# Sheet4.net
KiCad netlist of a schematic drawn in Altium Designer
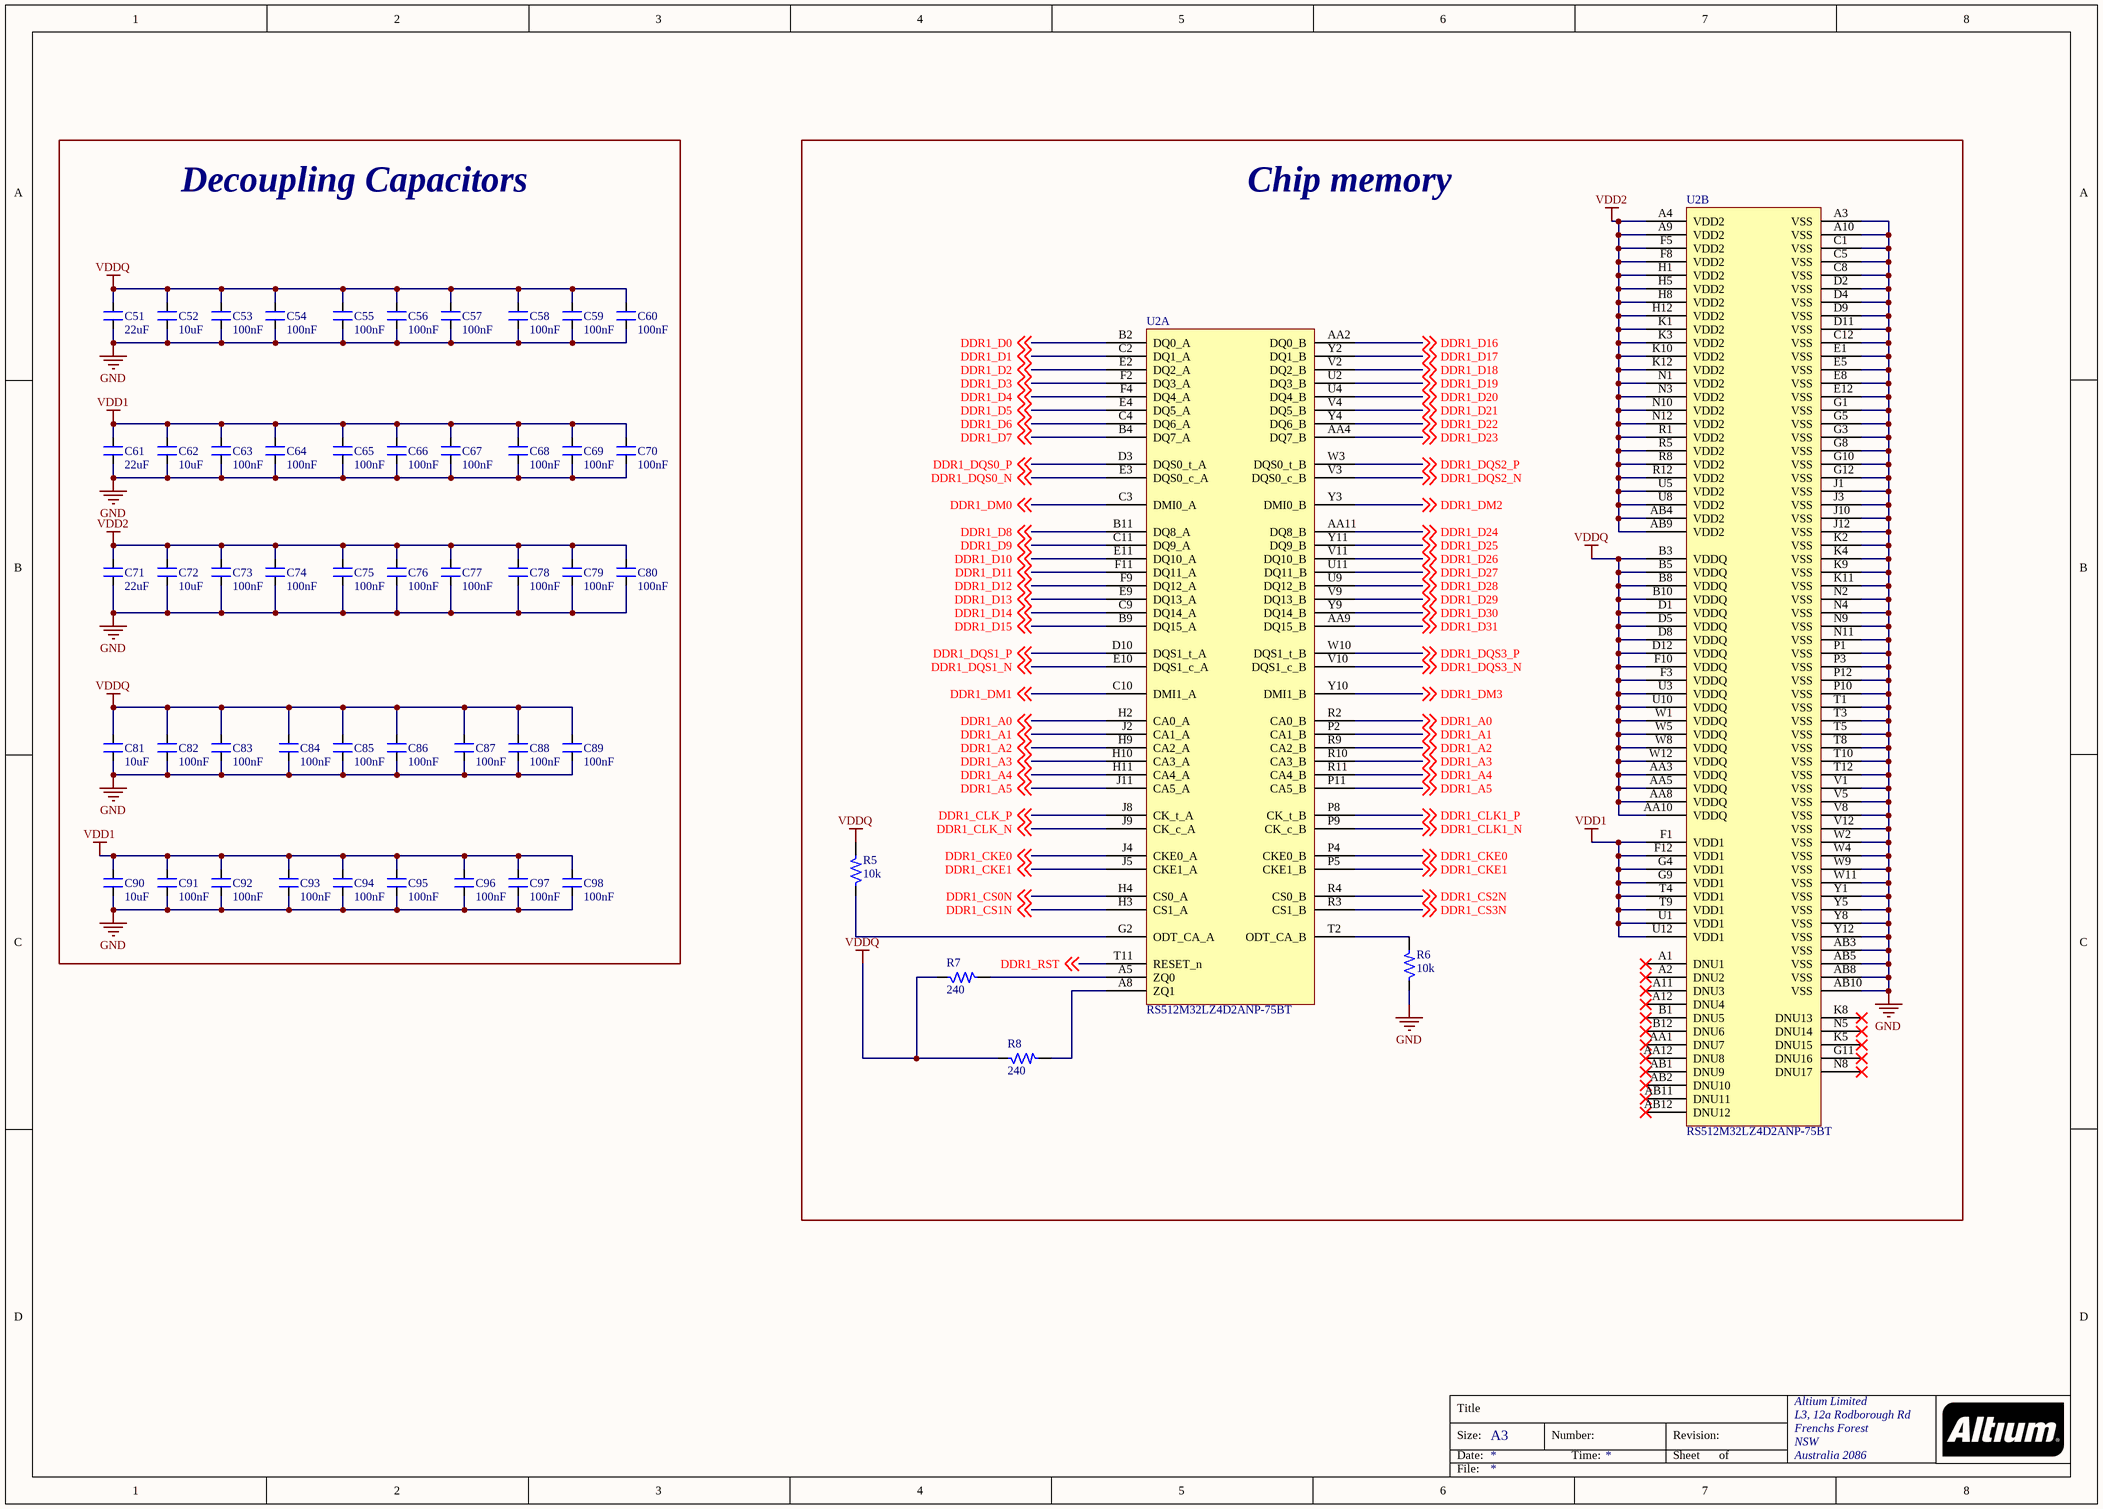
[diagram p0: Sheet4.SchDoc]

(export (version "E")
  (design (tool "Eeschema 10.0.6"))
  (components
    (comp (ref "C51")
      (value "22uF")
      (footprint "CAP_0603")
      (description "22µF ±20% 10V Ceramic Capacitor X5R 0603 (1608 Metric)")
      (fields
        (field (name "MANUFACTURER") "Murata Electronics")
        (field (name "MANUFACTURER PART NUMBER") "GRM188R61A226ME15D")
      )
      (libsource (lib "EsteemPCB_SOM_Course_intlib") (part "CAP_22uF-10V-20%-0603"))
    )
    (comp (ref "C52")
      (value "10uF")
      (footprint "CAP_0603")
      (description "10µF ±10% 10V Ceramic Capacitor X5R 0603 (1608 Metric)")
      (fields
        (field (name "MANUFACTURER PART NUMBER") "GRM188R61A106KE69J")
        (field (name "MANUFACTURER") "Murata Electronics")
      )
      (libsource (lib "EsteemPCB_SOM_Course_intlib") (part "CAP_10uF-10V-10%-0603"))
    )
    (comp (ref "C53")
      (value "100nF")
      (footprint "CAP_0201")
      (description "0.1µF ±10% 25V Ceramic Capacitor X5R 0201 (0603 Metric)")
      (fields
        (field (name "MANUFACTURER") "TDK Corporation")
        (field (name "MANUFACTURER PART NUMBER") "C0603X5R1E104K030BB")
      )
      (libsource (lib "EsteemPCB_SOM_Course_intlib") (part "CAP_100nF-25V-10%-0201"))
    )
    (comp (ref "C54")
      (value "100nF")
      (footprint "CAP_0201")
      (description "0.1µF ±10% 25V Ceramic Capacitor X5R 0201 (0603 Metric)")
      (fields
        (field (name "MANUFACTURER") "TDK Corporation")
        (field (name "MANUFACTURER PART NUMBER") "C0603X5R1E104K030BB")
      )
      (libsource (lib "EsteemPCB_SOM_Course_intlib") (part "CAP_100nF-25V-10%-0201"))
    )
    (comp (ref "C55")
      (value "100nF")
      (footprint "CAP_0201")
      (description "0.1µF ±10% 25V Ceramic Capacitor X5R 0201 (0603 Metric)")
      (fields
        (field (name "MANUFACTURER") "TDK Corporation")
        (field (name "MANUFACTURER PART NUMBER") "C0603X5R1E104K030BB")
      )
      (libsource (lib "EsteemPCB_SOM_Course_intlib") (part "CAP_100nF-25V-10%-0201"))
    )
    (comp (ref "C56")
      (value "100nF")
      (footprint "CAP_0201")
      (description "0.1µF ±10% 25V Ceramic Capacitor X5R 0201 (0603 Metric)")
      (fields
        (field (name "MANUFACTURER") "TDK Corporation")
        (field (name "MANUFACTURER PART NUMBER") "C0603X5R1E104K030BB")
      )
      (libsource (lib "EsteemPCB_SOM_Course_intlib") (part "CAP_100nF-25V-10%-0201"))
    )
    (comp (ref "C57")
      (value "100nF")
      (footprint "CAP_0201")
      (description "0.1µF ±10% 25V Ceramic Capacitor X5R 0201 (0603 Metric)")
      (fields
        (field (name "MANUFACTURER") "TDK Corporation")
        (field (name "MANUFACTURER PART NUMBER") "C0603X5R1E104K030BB")
      )
      (libsource (lib "EsteemPCB_SOM_Course_intlib") (part "CAP_100nF-25V-10%-0201"))
    )
    (comp (ref "C58")
      (value "100nF")
      (footprint "CAP_0201")
      (description "0.1µF ±10% 25V Ceramic Capacitor X5R 0201 (0603 Metric)")
      (fields
        (field (name "MANUFACTURER") "TDK Corporation")
        (field (name "MANUFACTURER PART NUMBER") "C0603X5R1E104K030BB")
      )
      (libsource (lib "EsteemPCB_SOM_Course_intlib") (part "CAP_100nF-25V-10%-0201"))
    )
    (comp (ref "C59")
      (value "100nF")
      (footprint "CAP_0201")
      (description "0.1µF ±10% 25V Ceramic Capacitor X5R 0201 (0603 Metric)")
      (fields
        (field (name "MANUFACTURER") "TDK Corporation")
        (field (name "MANUFACTURER PART NUMBER") "C0603X5R1E104K030BB")
      )
      (libsource (lib "EsteemPCB_SOM_Course_intlib") (part "CAP_100nF-25V-10%-0201"))
    )
    (comp (ref "C60")
      (value "100nF")
      (footprint "CAP_0201")
      (description "0.1µF ±10% 25V Ceramic Capacitor X5R 0201 (0603 Metric)")
      (fields
        (field (name "MANUFACTURER") "TDK Corporation")
        (field (name "MANUFACTURER PART NUMBER") "C0603X5R1E104K030BB")
      )
      (libsource (lib "EsteemPCB_SOM_Course_intlib") (part "CAP_100nF-25V-10%-0201"))
    )
    (comp (ref "C61")
      (value "22uF")
      (footprint "CAP_0603")
      (description "22µF ±20% 10V Ceramic Capacitor X5R 0603 (1608 Metric)")
      (fields
        (field (name "MANUFACTURER") "Murata Electronics")
        (field (name "MANUFACTURER PART NUMBER") "GRM188R61A226ME15D")
      )
      (libsource (lib "EsteemPCB_SOM_Course_intlib") (part "CAP_22uF-10V-20%-0603"))
    )
    (comp (ref "C62")
      (value "10uF")
      (footprint "CAP_0603")
      (description "10µF ±10% 10V Ceramic Capacitor X5R 0603 (1608 Metric)")
      (fields
        (field (name "MANUFACTURER PART NUMBER") "GRM188R61A106KE69J")
        (field (name "MANUFACTURER") "Murata Electronics")
      )
      (libsource (lib "EsteemPCB_SOM_Course_intlib") (part "CAP_10uF-10V-10%-0603"))
    )
    (comp (ref "C63")
      (value "100nF")
      (footprint "CAP_0201")
      (description "0.1µF ±10% 25V Ceramic Capacitor X5R 0201 (0603 Metric)")
      (fields
        (field (name "MANUFACTURER") "TDK Corporation")
        (field (name "MANUFACTURER PART NUMBER") "C0603X5R1E104K030BB")
      )
      (libsource (lib "EsteemPCB_SOM_Course_intlib") (part "CAP_100nF-25V-10%-0201"))
    )
    (comp (ref "C64")
      (value "100nF")
      (footprint "CAP_0201")
      (description "0.1µF ±10% 25V Ceramic Capacitor X5R 0201 (0603 Metric)")
      (fields
        (field (name "MANUFACTURER") "TDK Corporation")
        (field (name "MANUFACTURER PART NUMBER") "C0603X5R1E104K030BB")
      )
      (libsource (lib "EsteemPCB_SOM_Course_intlib") (part "CAP_100nF-25V-10%-0201"))
    )
    (comp (ref "C65")
      (value "100nF")
      (footprint "CAP_0201")
      (description "0.1µF ±10% 25V Ceramic Capacitor X5R 0201 (0603 Metric)")
      (fields
        (field (name "MANUFACTURER") "TDK Corporation")
        (field (name "MANUFACTURER PART NUMBER") "C0603X5R1E104K030BB")
      )
      (libsource (lib "EsteemPCB_SOM_Course_intlib") (part "CAP_100nF-25V-10%-0201"))
    )
    (comp (ref "C66")
      (value "100nF")
      (footprint "CAP_0201")
      (description "0.1µF ±10% 25V Ceramic Capacitor X5R 0201 (0603 Metric)")
      (fields
        (field (name "MANUFACTURER") "TDK Corporation")
        (field (name "MANUFACTURER PART NUMBER") "C0603X5R1E104K030BB")
      )
      (libsource (lib "EsteemPCB_SOM_Course_intlib") (part "CAP_100nF-25V-10%-0201"))
    )
    (comp (ref "C67")
      (value "100nF")
      (footprint "CAP_0201")
      (description "0.1µF ±10% 25V Ceramic Capacitor X5R 0201 (0603 Metric)")
      (fields
        (field (name "MANUFACTURER") "TDK Corporation")
        (field (name "MANUFACTURER PART NUMBER") "C0603X5R1E104K030BB")
      )
      (libsource (lib "EsteemPCB_SOM_Course_intlib") (part "CAP_100nF-25V-10%-0201"))
    )
    (comp (ref "C68")
      (value "100nF")
      (footprint "CAP_0201")
      (description "0.1µF ±10% 25V Ceramic Capacitor X5R 0201 (0603 Metric)")
      (fields
        (field (name "MANUFACTURER") "TDK Corporation")
        (field (name "MANUFACTURER PART NUMBER") "C0603X5R1E104K030BB")
      )
      (libsource (lib "EsteemPCB_SOM_Course_intlib") (part "CAP_100nF-25V-10%-0201"))
    )
    (comp (ref "C69")
      (value "100nF")
      (footprint "CAP_0201")
      (description "0.1µF ±10% 25V Ceramic Capacitor X5R 0201 (0603 Metric)")
      (fields
        (field (name "MANUFACTURER") "TDK Corporation")
        (field (name "MANUFACTURER PART NUMBER") "C0603X5R1E104K030BB")
      )
      (libsource (lib "EsteemPCB_SOM_Course_intlib") (part "CAP_100nF-25V-10%-0201"))
    )
    (comp (ref "C70")
      (value "100nF")
      (footprint "CAP_0201")
      (description "0.1µF ±10% 25V Ceramic Capacitor X5R 0201 (0603 Metric)")
      (fields
        (field (name "MANUFACTURER") "TDK Corporation")
        (field (name "MANUFACTURER PART NUMBER") "C0603X5R1E104K030BB")
      )
      (libsource (lib "EsteemPCB_SOM_Course_intlib") (part "CAP_100nF-25V-10%-0201"))
    )
    (comp (ref "C71")
      (value "22uF")
      (footprint "CAP_0603")
      (description "22µF ±20% 10V Ceramic Capacitor X5R 0603 (1608 Metric)")
      (fields
        (field (name "MANUFACTURER") "Murata Electronics")
        (field (name "MANUFACTURER PART NUMBER") "GRM188R61A226ME15D")
      )
      (libsource (lib "EsteemPCB_SOM_Course_intlib") (part "CAP_22uF-10V-20%-0603"))
    )
    (comp (ref "C72")
      (value "10uF")
      (footprint "CAP_0603")
      (description "10µF ±10% 10V Ceramic Capacitor X5R 0603 (1608 Metric)")
      (fields
        (field (name "MANUFACTURER PART NUMBER") "GRM188R61A106KE69J")
        (field (name "MANUFACTURER") "Murata Electronics")
      )
      (libsource (lib "EsteemPCB_SOM_Course_intlib") (part "CAP_10uF-10V-10%-0603"))
    )
    (comp (ref "C73")
      (value "100nF")
      (footprint "CAP_0201")
      (description "0.1µF ±10% 25V Ceramic Capacitor X5R 0201 (0603 Metric)")
      (fields
        (field (name "MANUFACTURER") "TDK Corporation")
        (field (name "MANUFACTURER PART NUMBER") "C0603X5R1E104K030BB")
      )
      (libsource (lib "EsteemPCB_SOM_Course_intlib") (part "CAP_100nF-25V-10%-0201"))
    )
    (comp (ref "C74")
      (value "100nF")
      (footprint "CAP_0201")
      (description "0.1µF ±10% 25V Ceramic Capacitor X5R 0201 (0603 Metric)")
      (fields
        (field (name "MANUFACTURER") "TDK Corporation")
        (field (name "MANUFACTURER PART NUMBER") "C0603X5R1E104K030BB")
      )
      (libsource (lib "EsteemPCB_SOM_Course_intlib") (part "CAP_100nF-25V-10%-0201"))
    )
    (comp (ref "C75")
      (value "100nF")
      (footprint "CAP_0201")
      (description "0.1µF ±10% 25V Ceramic Capacitor X5R 0201 (0603 Metric)")
      (fields
        (field (name "MANUFACTURER") "TDK Corporation")
        (field (name "MANUFACTURER PART NUMBER") "C0603X5R1E104K030BB")
      )
      (libsource (lib "EsteemPCB_SOM_Course_intlib") (part "CAP_100nF-25V-10%-0201"))
    )
    (comp (ref "C76")
      (value "100nF")
      (footprint "CAP_0201")
      (description "0.1µF ±10% 25V Ceramic Capacitor X5R 0201 (0603 Metric)")
      (fields
        (field (name "MANUFACTURER") "TDK Corporation")
        (field (name "MANUFACTURER PART NUMBER") "C0603X5R1E104K030BB")
      )
      (libsource (lib "EsteemPCB_SOM_Course_intlib") (part "CAP_100nF-25V-10%-0201"))
    )
    (comp (ref "C77")
      (value "100nF")
      (footprint "CAP_0201")
      (description "0.1µF ±10% 25V Ceramic Capacitor X5R 0201 (0603 Metric)")
      (fields
        (field (name "MANUFACTURER") "TDK Corporation")
        (field (name "MANUFACTURER PART NUMBER") "C0603X5R1E104K030BB")
      )
      (libsource (lib "EsteemPCB_SOM_Course_intlib") (part "CAP_100nF-25V-10%-0201"))
    )
    (comp (ref "C78")
      (value "100nF")
      (footprint "CAP_0201")
      (description "0.1µF ±10% 25V Ceramic Capacitor X5R 0201 (0603 Metric)")
      (fields
        (field (name "MANUFACTURER") "TDK Corporation")
        (field (name "MANUFACTURER PART NUMBER") "C0603X5R1E104K030BB")
      )
      (libsource (lib "EsteemPCB_SOM_Course_intlib") (part "CAP_100nF-25V-10%-0201"))
    )
    (comp (ref "C79")
      (value "100nF")
      (footprint "CAP_0201")
      (description "0.1µF ±10% 25V Ceramic Capacitor X5R 0201 (0603 Metric)")
      (fields
        (field (name "MANUFACTURER") "TDK Corporation")
        (field (name "MANUFACTURER PART NUMBER") "C0603X5R1E104K030BB")
      )
      (libsource (lib "EsteemPCB_SOM_Course_intlib") (part "CAP_100nF-25V-10%-0201"))
    )
    (comp (ref "C80")
      (value "100nF")
      (footprint "CAP_0201")
      (description "0.1µF ±10% 25V Ceramic Capacitor X5R 0201 (0603 Metric)")
      (fields
        (field (name "MANUFACTURER") "TDK Corporation")
        (field (name "MANUFACTURER PART NUMBER") "C0603X5R1E104K030BB")
      )
      (libsource (lib "EsteemPCB_SOM_Course_intlib") (part "CAP_100nF-25V-10%-0201"))
    )
    (comp (ref "C81")
      (value "10uF")
      (footprint "CAP_0603")
      (description "10µF ±10% 10V Ceramic Capacitor X5R 0603 (1608 Metric)")
      (fields
        (field (name "MANUFACTURER PART NUMBER") "GRM188R61A106KE69J")
        (field (name "MANUFACTURER") "Murata Electronics")
      )
      (libsource (lib "EsteemPCB_SOM_Course_intlib") (part "CAP_10uF-10V-10%-0603"))
    )
    (comp (ref "C82")
      (value "100nF")
      (footprint "CAP_0201")
      (description "0.1µF ±10% 25V Ceramic Capacitor X5R 0201 (0603 Metric)")
      (fields
        (field (name "MANUFACTURER") "TDK Corporation")
        (field (name "MANUFACTURER PART NUMBER") "C0603X5R1E104K030BB")
      )
      (libsource (lib "EsteemPCB_SOM_Course_intlib") (part "CAP_100nF-25V-10%-0201"))
    )
    (comp (ref "C83")
      (value "100nF")
      (footprint "CAP_0201")
      (description "0.1µF ±10% 25V Ceramic Capacitor X5R 0201 (0603 Metric)")
      (fields
        (field (name "MANUFACTURER") "TDK Corporation")
        (field (name "MANUFACTURER PART NUMBER") "C0603X5R1E104K030BB")
      )
      (libsource (lib "EsteemPCB_SOM_Course_intlib") (part "CAP_100nF-25V-10%-0201"))
    )
    (comp (ref "C84")
      (value "100nF")
      (footprint "CAP_0201")
      (description "0.1µF ±10% 25V Ceramic Capacitor X5R 0201 (0603 Metric)")
      (fields
        (field (name "MANUFACTURER") "TDK Corporation")
        (field (name "MANUFACTURER PART NUMBER") "C0603X5R1E104K030BB")
      )
      (libsource (lib "EsteemPCB_SOM_Course_intlib") (part "CAP_100nF-25V-10%-0201"))
    )
    (comp (ref "C85")
      (value "100nF")
      (footprint "CAP_0201")
      (description "0.1µF ±10% 25V Ceramic Capacitor X5R 0201 (0603 Metric)")
      (fields
        (field (name "MANUFACTURER") "TDK Corporation")
        (field (name "MANUFACTURER PART NUMBER") "C0603X5R1E104K030BB")
      )
      (libsource (lib "EsteemPCB_SOM_Course_intlib") (part "CAP_100nF-25V-10%-0201"))
    )
    (comp (ref "C86")
      (value "100nF")
      (footprint "CAP_0201")
      (description "0.1µF ±10% 25V Ceramic Capacitor X5R 0201 (0603 Metric)")
      (fields
        (field (name "MANUFACTURER") "TDK Corporation")
        (field (name "MANUFACTURER PART NUMBER") "C0603X5R1E104K030BB")
      )
      (libsource (lib "EsteemPCB_SOM_Course_intlib") (part "CAP_100nF-25V-10%-0201"))
    )
    (comp (ref "C87")
      (value "100nF")
      (footprint "CAP_0201")
      (description "0.1µF ±10% 25V Ceramic Capacitor X5R 0201 (0603 Metric)")
      (fields
        (field (name "MANUFACTURER") "TDK Corporation")
        (field (name "MANUFACTURER PART NUMBER") "C0603X5R1E104K030BB")
      )
      (libsource (lib "EsteemPCB_SOM_Course_intlib") (part "CAP_100nF-25V-10%-0201"))
    )
    (comp (ref "C88")
      (value "100nF")
      (footprint "CAP_0201")
      (description "0.1µF ±10% 25V Ceramic Capacitor X5R 0201 (0603 Metric)")
      (fields
        (field (name "MANUFACTURER") "TDK Corporation")
        (field (name "MANUFACTURER PART NUMBER") "C0603X5R1E104K030BB")
      )
      (libsource (lib "EsteemPCB_SOM_Course_intlib") (part "CAP_100nF-25V-10%-0201"))
    )
    (comp (ref "C89")
      (value "100nF")
      (footprint "CAP_0201")
      (description "0.1µF ±10% 25V Ceramic Capacitor X5R 0201 (0603 Metric)")
      (fields
        (field (name "MANUFACTURER") "TDK Corporation")
        (field (name "MANUFACTURER PART NUMBER") "C0603X5R1E104K030BB")
      )
      (libsource (lib "EsteemPCB_SOM_Course_intlib") (part "CAP_100nF-25V-10%-0201"))
    )
    (comp (ref "C90")
      (value "10uF")
      (footprint "CAP_0603")
      (description "10µF ±10% 10V Ceramic Capacitor X5R 0603 (1608 Metric)")
      (fields
        (field (name "MANUFACTURER PART NUMBER") "GRM188R61A106KE69J")
        (field (name "MANUFACTURER") "Murata Electronics")
      )
      (libsource (lib "EsteemPCB_SOM_Course_intlib") (part "CAP_10uF-10V-10%-0603"))
    )
    (comp (ref "C91")
      (value "100nF")
      (footprint "CAP_0201")
      (description "0.1µF ±10% 25V Ceramic Capacitor X5R 0201 (0603 Metric)")
      (fields
        (field (name "MANUFACTURER") "TDK Corporation")
        (field (name "MANUFACTURER PART NUMBER") "C0603X5R1E104K030BB")
      )
      (libsource (lib "EsteemPCB_SOM_Course_intlib") (part "CAP_100nF-25V-10%-0201"))
    )
    (comp (ref "C92")
      (value "100nF")
      (footprint "CAP_0201")
      (description "0.1µF ±10% 25V Ceramic Capacitor X5R 0201 (0603 Metric)")
      (fields
        (field (name "MANUFACTURER") "TDK Corporation")
        (field (name "MANUFACTURER PART NUMBER") "C0603X5R1E104K030BB")
      )
      (libsource (lib "EsteemPCB_SOM_Course_intlib") (part "CAP_100nF-25V-10%-0201"))
    )
    (comp (ref "C93")
      (value "100nF")
      (footprint "CAP_0201")
      (description "0.1µF ±10% 25V Ceramic Capacitor X5R 0201 (0603 Metric)")
      (fields
        (field (name "MANUFACTURER") "TDK Corporation")
        (field (name "MANUFACTURER PART NUMBER") "C0603X5R1E104K030BB")
      )
      (libsource (lib "EsteemPCB_SOM_Course_intlib") (part "CAP_100nF-25V-10%-0201"))
    )
    (comp (ref "C94")
      (value "100nF")
      (footprint "CAP_0201")
      (description "0.1µF ±10% 25V Ceramic Capacitor X5R 0201 (0603 Metric)")
      (fields
        (field (name "MANUFACTURER") "TDK Corporation")
        (field (name "MANUFACTURER PART NUMBER") "C0603X5R1E104K030BB")
      )
      (libsource (lib "EsteemPCB_SOM_Course_intlib") (part "CAP_100nF-25V-10%-0201"))
    )
    (comp (ref "C95")
      (value "100nF")
      (footprint "CAP_0201")
      (description "0.1µF ±10% 25V Ceramic Capacitor X5R 0201 (0603 Metric)")
      (fields
        (field (name "MANUFACTURER") "TDK Corporation")
        (field (name "MANUFACTURER PART NUMBER") "C0603X5R1E104K030BB")
      )
      (libsource (lib "EsteemPCB_SOM_Course_intlib") (part "CAP_100nF-25V-10%-0201"))
    )
    (comp (ref "C96")
      (value "100nF")
      (footprint "CAP_0201")
      (description "0.1µF ±10% 25V Ceramic Capacitor X5R 0201 (0603 Metric)")
      (fields
        (field (name "MANUFACTURER") "TDK Corporation")
        (field (name "MANUFACTURER PART NUMBER") "C0603X5R1E104K030BB")
      )
      (libsource (lib "EsteemPCB_SOM_Course_intlib") (part "CAP_100nF-25V-10%-0201"))
    )
    (comp (ref "C97")
      (value "100nF")
      (footprint "CAP_0201")
      (description "0.1µF ±10% 25V Ceramic Capacitor X5R 0201 (0603 Metric)")
      (fields
        (field (name "MANUFACTURER") "TDK Corporation")
        (field (name "MANUFACTURER PART NUMBER") "C0603X5R1E104K030BB")
      )
      (libsource (lib "EsteemPCB_SOM_Course_intlib") (part "CAP_100nF-25V-10%-0201"))
    )
    (comp (ref "C98")
      (value "100nF")
      (footprint "CAP_0201")
      (description "0.1µF ±10% 25V Ceramic Capacitor X5R 0201 (0603 Metric)")
      (fields
        (field (name "MANUFACTURER") "TDK Corporation")
        (field (name "MANUFACTURER PART NUMBER") "C0603X5R1E104K030BB")
      )
      (libsource (lib "EsteemPCB_SOM_Course_intlib") (part "CAP_100nF-25V-10%-0201"))
    )
    (comp (ref "R5")
      (value "10k")
      (footprint "RES_0201")
      (description "0 Ohms Jumper 0.05W, 1/20W Chip Resistor 0201 (0603 Metric) Automotive AEC-Q200 Thick Film")
      (fields
        (field (name "MANUFACTURER") "Bourns Inc.")
        (field (name "MANUFACTURER PART NUMBER") "CR0201AJ/-000GLF")
      )
      (libsource (lib "EsteemPCB_SOM_Course_intlib") (part "RES_0R-0.05W-1%-0201"))
    )
    (comp (ref "R6")
      (value "10k")
      (footprint "RES_0201")
      (description "0 Ohms Jumper 0.05W, 1/20W Chip Resistor 0201 (0603 Metric) Automotive AEC-Q200 Thick Film")
      (fields
        (field (name "MANUFACTURER") "Bourns Inc.")
        (field (name "MANUFACTURER PART NUMBER") "CR0201AJ/-000GLF")
      )
      (libsource (lib "EsteemPCB_SOM_Course_intlib") (part "RES_0R-0.05W-1%-0201"))
    )
    (comp (ref "R7")
      (value "240")
      (footprint "RES_0201")
      (description "0 Ohms Jumper 0.05W, 1/20W Chip Resistor 0201 (0603 Metric) Automotive AEC-Q200 Thick Film")
      (fields
        (field (name "MANUFACTURER") "Bourns Inc.")
        (field (name "MANUFACTURER PART NUMBER") "CR0201AJ/-000GLF")
      )
      (libsource (lib "EsteemPCB_SOM_Course_intlib") (part "RES_0R-0.05W-1%-0201"))
    )
    (comp (ref "R8")
      (value "240")
      (footprint "RES_0201")
      (description "0 Ohms Jumper 0.05W, 1/20W Chip Resistor 0201 (0603 Metric) Automotive AEC-Q200 Thick Film")
      (fields
        (field (name "MANUFACTURER") "Bourns Inc.")
        (field (name "MANUFACTURER PART NUMBER") "CR0201AJ/-000GLF")
      )
      (libsource (lib "EsteemPCB_SOM_Course_intlib") (part "RES_0R-0.05W-1%-0201"))
    )
    (comp (ref "U2")
      (value "RS512M32LZ4D2ANP-75BT")
      (footprint "FBGA200_SMD")
      (fields (field (name "MANUFACTURER") "RAYSON"))
      (libsource (lib "RK3399 _Module_Schlib") (part "IC_RS512M32LZ4D2ANP-75BT"))
    )
  )
  (nets
    (net (code "1") (name "DDR1_A0") (class "Default")
      (node (ref "U2") (pin "H2") (pinfunction "CA0_A_H2") (pintype "passive"))
      (node (ref "U2") (pin "R2") (pinfunction "CA0_B_R2") (pintype "passive"))
    )
    (net (code "2") (name "DDR1_A1") (class "Default")
      (node (ref "U2") (pin "J2") (pinfunction "CA1_A_J2") (pintype "passive"))
      (node (ref "U2") (pin "P2") (pinfunction "CA1_B_P2") (pintype "passive"))
    )
    (net (code "3") (name "DDR1_A2") (class "Default")
      (node (ref "U2") (pin "H9") (pinfunction "CA2_A_H9") (pintype "passive"))
      (node (ref "U2") (pin "R9") (pinfunction "CA2_B_R9") (pintype "passive"))
    )
    (net (code "4") (name "DDR1_A3") (class "Default")
      (node (ref "U2") (pin "H10") (pinfunction "CA3_A_H10") (pintype "passive"))
      (node (ref "U2") (pin "R10") (pinfunction "CA3_B_R10") (pintype "passive"))
    )
    (net (code "5") (name "DDR1_A4") (class "Default")
      (node (ref "U2") (pin "H11") (pinfunction "CA4_A_H11") (pintype "passive"))
      (node (ref "U2") (pin "R11") (pinfunction "CA4_B_R11") (pintype "passive"))
    )
    (net (code "6") (name "DDR1_A5") (class "Default")
      (node (ref "U2") (pin "J11") (pinfunction "CA5_A_J11") (pintype "passive"))
      (node (ref "U2") (pin "P11") (pinfunction "CA5_B_P11") (pintype "passive"))
    )
    (net (code "7") (name "DDR1_CKE0") (class "Default")
      (node (ref "U2") (pin "J4") (pinfunction "CKE0_A_J4") (pintype "passive"))
      (node (ref "U2") (pin "P4") (pinfunction "CKE0_B_P4") (pintype "passive"))
    )
    (net (code "8") (name "DDR1_CKE1") (class "Default")
      (node (ref "U2") (pin "J5") (pinfunction "CKE1_A_J5") (pintype "passive"))
      (node (ref "U2") (pin "P5") (pinfunction "CKE1_B_P5") (pintype "passive"))
    )
    (net (code "9") (name "DDR1_CLK1_N") (class "Default")
      (node (ref "U2") (pin "P9") (pinfunction "CK_c_B_P9") (pintype "passive"))
    )
    (net (code "10") (name "DDR1_CLK1_P") (class "Default")
      (node (ref "U2") (pin "P8") (pinfunction "CK_t_B_P8") (pintype "passive"))
    )
    (net (code "11") (name "DDR1_CLK_N") (class "Default")
      (node (ref "U2") (pin "J9") (pinfunction "CK_c_A_J9") (pintype "passive"))
    )
    (net (code "12") (name "DDR1_CLK_P") (class "Default")
      (node (ref "U2") (pin "J8") (pinfunction "CK_t_A_J8") (pintype "passive"))
    )
    (net (code "13") (name "DDR1_CS0N") (class "Default")
      (node (ref "U2") (pin "H4") (pinfunction "CS0_A_H4") (pintype "passive"))
    )
    (net (code "14") (name "DDR1_CS1N") (class "Default")
      (node (ref "U2") (pin "H3") (pinfunction "CS1_A_H3") (pintype "passive"))
    )
    (net (code "15") (name "DDR1_CS2N") (class "Default")
      (node (ref "U2") (pin "R4") (pinfunction "CS0_B_R4") (pintype "passive"))
    )
    (net (code "16") (name "DDR1_CS3N") (class "Default")
      (node (ref "U2") (pin "R3") (pinfunction "CS1_B_R3") (pintype "passive"))
    )
    (net (code "17") (name "DDR1_D0") (class "Default")
      (node (ref "U2") (pin "B2") (pinfunction "DQ0_A_B2") (pintype "passive"))
    )
    (net (code "18") (name "DDR1_D1") (class "Default")
      (node (ref "U2") (pin "C2") (pinfunction "DQ1_A_C2") (pintype "passive"))
    )
    (net (code "19") (name "DDR1_D2") (class "Default")
      (node (ref "U2") (pin "E2") (pinfunction "DQ2_A_E2") (pintype "passive"))
    )
    (net (code "20") (name "DDR1_D3") (class "Default")
      (node (ref "U2") (pin "F2") (pinfunction "DQ3_A_F2") (pintype "passive"))
    )
    (net (code "21") (name "DDR1_D4") (class "Default")
      (node (ref "U2") (pin "F4") (pinfunction "DQ4_A_F4") (pintype "passive"))
    )
    (net (code "22") (name "DDR1_D5") (class "Default")
      (node (ref "U2") (pin "E4") (pinfunction "DQ5_A_E4") (pintype "passive"))
    )
    (net (code "23") (name "DDR1_D6") (class "Default")
      (node (ref "U2") (pin "C4") (pinfunction "DQ6_A_C4") (pintype "passive"))
    )
    (net (code "24") (name "DDR1_D7") (class "Default")
      (node (ref "U2") (pin "B4") (pinfunction "DQ7_A_B4") (pintype "passive"))
    )
    (net (code "25") (name "DDR1_D8") (class "Default")
      (node (ref "U2") (pin "B11") (pinfunction "DQ8_A_B11") (pintype "passive"))
    )
    (net (code "26") (name "DDR1_D9") (class "Default")
      (node (ref "U2") (pin "C11") (pinfunction "DQ9_A_C11") (pintype "passive"))
    )
    (net (code "27") (name "DDR1_D10") (class "Default")
      (node (ref "U2") (pin "E11") (pinfunction "DQ10_A_E11") (pintype "passive"))
    )
    (net (code "28") (name "DDR1_D11") (class "Default")
      (node (ref "U2") (pin "F11") (pinfunction "DQ11_A_F11") (pintype "passive"))
    )
    (net (code "29") (name "DDR1_D12") (class "Default")
      (node (ref "U2") (pin "F9") (pinfunction "DQ12_A_F9") (pintype "passive"))
    )
    (net (code "30") (name "DDR1_D13") (class "Default")
      (node (ref "U2") (pin "E9") (pinfunction "DQ13_A_E9") (pintype "passive"))
    )
    (net (code "31") (name "DDR1_D14") (class "Default")
      (node (ref "U2") (pin "C9") (pinfunction "DQ14_A_C9") (pintype "passive"))
    )
    (net (code "32") (name "DDR1_D15") (class "Default")
      (node (ref "U2") (pin "B9") (pinfunction "DQ15_A_B9") (pintype "passive"))
    )
    (net (code "33") (name "DDR1_D16") (class "Default")
      (node (ref "U2") (pin "AA2") (pinfunction "DQ0_B_AA2") (pintype "passive"))
    )
    (net (code "34") (name "DDR1_D17") (class "Default")
      (node (ref "U2") (pin "Y2") (pinfunction "DQ1_B_Y2") (pintype "passive"))
    )
    (net (code "35") (name "DDR1_D18") (class "Default")
      (node (ref "U2") (pin "V2") (pinfunction "DQ2_B_V2") (pintype "passive"))
    )
    (net (code "36") (name "DDR1_D19") (class "Default")
      (node (ref "U2") (pin "U2") (pinfunction "DQ3_B_U2") (pintype "passive"))
    )
    (net (code "37") (name "DDR1_D20") (class "Default")
      (node (ref "U2") (pin "U4") (pinfunction "DQ4_B_U4") (pintype "passive"))
    )
    (net (code "38") (name "DDR1_D21") (class "Default")
      (node (ref "U2") (pin "V4") (pinfunction "DQ5_B_V4") (pintype "passive"))
    )
    (net (code "39") (name "DDR1_D22") (class "Default")
      (node (ref "U2") (pin "Y4") (pinfunction "DQ6_B_Y4") (pintype "passive"))
    )
    (net (code "40") (name "DDR1_D23") (class "Default")
      (node (ref "U2") (pin "AA4") (pinfunction "DQ7_B_AA4") (pintype "passive"))
    )
    (net (code "41") (name "DDR1_D24") (class "Default")
      (node (ref "U2") (pin "AA11") (pinfunction "DQ8_B_AA11") (pintype "passive"))
    )
    (net (code "42") (name "DDR1_D25") (class "Default")
      (node (ref "U2") (pin "Y11") (pinfunction "DQ9_B_Y11") (pintype "passive"))
    )
    (net (code "43") (name "DDR1_D26") (class "Default")
      (node (ref "U2") (pin "V11") (pinfunction "DQ10_B_V11") (pintype "passive"))
    )
    (net (code "44") (name "DDR1_D27") (class "Default")
      (node (ref "U2") (pin "U11") (pinfunction "DQ11_B_U11") (pintype "passive"))
    )
    (net (code "45") (name "DDR1_D28") (class "Default")
      (node (ref "U2") (pin "U9") (pinfunction "DQ12_B_U9") (pintype "passive"))
    )
    (net (code "46") (name "DDR1_D29") (class "Default")
      (node (ref "U2") (pin "V9") (pinfunction "DQ13_B_V9") (pintype "passive"))
    )
    (net (code "47") (name "DDR1_D30") (class "Default")
      (node (ref "U2") (pin "Y9") (pinfunction "DQ14_B_Y9") (pintype "passive"))
    )
    (net (code "48") (name "DDR1_D31") (class "Default")
      (node (ref "U2") (pin "AA9") (pinfunction "DQ15_B_AA9") (pintype "passive"))
    )
    (net (code "49") (name "DDR1_DM0") (class "Default")
      (node (ref "U2") (pin "C3") (pinfunction "DMI0_A_C3") (pintype "passive"))
    )
    (net (code "50") (name "DDR1_DM1") (class "Default")
      (node (ref "U2") (pin "C10") (pinfunction "DMI1_A_C10") (pintype "passive"))
    )
    (net (code "51") (name "DDR1_DM2") (class "Default")
      (node (ref "U2") (pin "Y3") (pinfunction "DMI0_B_Y3") (pintype "passive"))
    )
    (net (code "52") (name "DDR1_DM3") (class "Default")
      (node (ref "U2") (pin "Y10") (pinfunction "DMI1_B_Y10") (pintype "passive"))
    )
    (net (code "53") (name "DDR1_DQS0_N") (class "Default")
      (node (ref "U2") (pin "E3") (pinfunction "DQS0_c_A_E3") (pintype "passive"))
    )
    (net (code "54") (name "DDR1_DQS0_P") (class "Default")
      (node (ref "U2") (pin "D3") (pinfunction "DQS0_t_A_D3") (pintype "passive"))
    )
    (net (code "55") (name "DDR1_DQS1_N") (class "Default")
      (node (ref "U2") (pin "E10") (pinfunction "DQS1_c_A_E10") (pintype "passive"))
    )
    (net (code "56") (name "DDR1_DQS1_P") (class "Default")
      (node (ref "U2") (pin "D10") (pinfunction "DQS1_t_A_D10") (pintype "passive"))
    )
    (net (code "57") (name "DDR1_DQS2_N") (class "Default")
      (node (ref "U2") (pin "V3") (pinfunction "DQS0_c_B_V3") (pintype "passive"))
    )
    (net (code "58") (name "DDR1_DQS2_P") (class "Default")
      (node (ref "U2") (pin "W3") (pinfunction "DQS0_t_B_W3") (pintype "passive"))
    )
    (net (code "59") (name "DDR1_DQS3_N") (class "Default")
      (node (ref "U2") (pin "V10") (pinfunction "DQS1_c_B_V10") (pintype "passive"))
    )
    (net (code "60") (name "DDR1_DQS3_P") (class "Default")
      (node (ref "U2") (pin "W10") (pinfunction "DQS1_t_B_W10") (pintype "passive"))
    )
    (net (code "61") (name "DDR1_RST") (class "Default")
      (node (ref "U2") (pin "T11") (pinfunction "RESET_n_T11") (pintype "passive"))
    )
    (net (code "62") (name "GND") (class "Default")
      (node (ref "C51") (pin "1") (pinfunction "1_1") (pintype "passive"))
      (node (ref "C52") (pin "1") (pinfunction "1_1") (pintype "passive"))
      (node (ref "C53") (pin "1") (pinfunction "1_1") (pintype "passive"))
      (node (ref "C54") (pin "1") (pinfunction "1_1") (pintype "passive"))
      (node (ref "C55") (pin "1") (pinfunction "1_1") (pintype "passive"))
      (node (ref "C56") (pin "1") (pinfunction "1_1") (pintype "passive"))
      (node (ref "C57") (pin "1") (pinfunction "1_1") (pintype "passive"))
      (node (ref "C58") (pin "1") (pinfunction "1_1") (pintype "passive"))
      (node (ref "C59") (pin "1") (pinfunction "1_1") (pintype "passive"))
      (node (ref "C60") (pin "1") (pinfunction "1_1") (pintype "passive"))
      (node (ref "C61") (pin "1") (pinfunction "1_1") (pintype "passive"))
      (node (ref "C62") (pin "1") (pinfunction "1_1") (pintype "passive"))
      (node (ref "C63") (pin "1") (pinfunction "1_1") (pintype "passive"))
      (node (ref "C64") (pin "1") (pinfunction "1_1") (pintype "passive"))
      (node (ref "C65") (pin "1") (pinfunction "1_1") (pintype "passive"))
      (node (ref "C66") (pin "1") (pinfunction "1_1") (pintype "passive"))
      (node (ref "C67") (pin "1") (pinfunction "1_1") (pintype "passive"))
      (node (ref "C68") (pin "1") (pinfunction "1_1") (pintype "passive"))
      (node (ref "C69") (pin "1") (pinfunction "1_1") (pintype "passive"))
      (node (ref "C70") (pin "1") (pinfunction "1_1") (pintype "passive"))
      (node (ref "C71") (pin "1") (pinfunction "1_1") (pintype "passive"))
      (node (ref "C72") (pin "1") (pinfunction "1_1") (pintype "passive"))
      (node (ref "C73") (pin "1") (pinfunction "1_1") (pintype "passive"))
      (node (ref "C74") (pin "1") (pinfunction "1_1") (pintype "passive"))
      (node (ref "C75") (pin "1") (pinfunction "1_1") (pintype "passive"))
      (node (ref "C76") (pin "1") (pinfunction "1_1") (pintype "passive"))
      (node (ref "C77") (pin "1") (pinfunction "1_1") (pintype "passive"))
      (node (ref "C78") (pin "1") (pinfunction "1_1") (pintype "passive"))
      (node (ref "C79") (pin "1") (pinfunction "1_1") (pintype "passive"))
      (node (ref "C80") (pin "1") (pinfunction "1_1") (pintype "passive"))
      (node (ref "C81") (pin "1") (pinfunction "1_1") (pintype "passive"))
      (node (ref "C82") (pin "1") (pinfunction "1_1") (pintype "passive"))
      (node (ref "C83") (pin "1") (pinfunction "1_1") (pintype "passive"))
      (node (ref "C84") (pin "1") (pinfunction "1_1") (pintype "passive"))
      (node (ref "C85") (pin "1") (pinfunction "1_1") (pintype "passive"))
      (node (ref "C86") (pin "1") (pinfunction "1_1") (pintype "passive"))
      (node (ref "C87") (pin "1") (pinfunction "1_1") (pintype "passive"))
      (node (ref "C88") (pin "1") (pinfunction "1_1") (pintype "passive"))
      (node (ref "C89") (pin "1") (pinfunction "1_1") (pintype "passive"))
      (node (ref "C90") (pin "1") (pinfunction "1_1") (pintype "passive"))
      (node (ref "C91") (pin "1") (pinfunction "1_1") (pintype "passive"))
      (node (ref "C92") (pin "1") (pinfunction "1_1") (pintype "passive"))
      (node (ref "C93") (pin "1") (pinfunction "1_1") (pintype "passive"))
      (node (ref "C94") (pin "1") (pinfunction "1_1") (pintype "passive"))
      (node (ref "C95") (pin "1") (pinfunction "1_1") (pintype "passive"))
      (node (ref "C96") (pin "1") (pinfunction "1_1") (pintype "passive"))
      (node (ref "C97") (pin "1") (pinfunction "1_1") (pintype "passive"))
      (node (ref "C98") (pin "1") (pinfunction "1_1") (pintype "passive"))
      (node (ref "R6") (pin "1") (pinfunction "1_1") (pintype "passive"))
      (node (ref "U2") (pin "A10") (pinfunction "VSS_A10") (pintype "passive"))
      (node (ref "U2") (pin "A3") (pinfunction "VSS_A3") (pintype "passive"))
      (node (ref "U2") (pin "AB10") (pinfunction "VSS_AB10") (pintype "passive"))
      (node (ref "U2") (pin "AB3") (pinfunction "VSS_AB3") (pintype "passive"))
      (node (ref "U2") (pin "AB5") (pinfunction "VSS_AB5") (pintype "passive"))
      (node (ref "U2") (pin "AB8") (pinfunction "VSS_AB8") (pintype "passive"))
      (node (ref "U2") (pin "C1") (pinfunction "VSS_C1") (pintype "passive"))
      (node (ref "U2") (pin "C12") (pinfunction "VSS_C12") (pintype "passive"))
      (node (ref "U2") (pin "C5") (pinfunction "VSS_C5") (pintype "passive"))
      (node (ref "U2") (pin "C8") (pinfunction "VSS_C8") (pintype "passive"))
      (node (ref "U2") (pin "D11") (pinfunction "VSS_D11") (pintype "passive"))
      (node (ref "U2") (pin "D2") (pinfunction "VSS_D2") (pintype "passive"))
      (node (ref "U2") (pin "D4") (pinfunction "VSS_D4") (pintype "passive"))
      (node (ref "U2") (pin "D9") (pinfunction "VSS_D9") (pintype "passive"))
      (node (ref "U2") (pin "E1") (pinfunction "VSS_E1") (pintype "passive"))
      (node (ref "U2") (pin "E12") (pinfunction "VSS_E12") (pintype "passive"))
      (node (ref "U2") (pin "E5") (pinfunction "VSS_E5") (pintype "passive"))
      (node (ref "U2") (pin "E8") (pinfunction "VSS_E8") (pintype "passive"))
      (node (ref "U2") (pin "G1") (pinfunction "VSS_G1") (pintype "passive"))
      (node (ref "U2") (pin "G10") (pinfunction "VSS_G10") (pintype "passive"))
      (node (ref "U2") (pin "G12") (pinfunction "VSS_G12") (pintype "passive"))
      (node (ref "U2") (pin "G3") (pinfunction "VSS_G3") (pintype "passive"))
      (node (ref "U2") (pin "G5") (pinfunction "VSS_G5") (pintype "passive"))
      (node (ref "U2") (pin "G8") (pinfunction "VSS_G8") (pintype "passive"))
      (node (ref "U2") (pin "J1") (pinfunction "VSS_J1") (pintype "passive"))
      (node (ref "U2") (pin "J10") (pinfunction "VSS_J10") (pintype "passive"))
      (node (ref "U2") (pin "J12") (pinfunction "VSS_J12") (pintype "passive"))
      (node (ref "U2") (pin "J3") (pinfunction "VSS_J3") (pintype "passive"))
      (node (ref "U2") (pin "K11") (pinfunction "VSS_K11") (pintype "passive"))
      (node (ref "U2") (pin "K2") (pinfunction "VSS_K2") (pintype "passive"))
      (node (ref "U2") (pin "K4") (pinfunction "VSS_K4") (pintype "passive"))
      (node (ref "U2") (pin "K9") (pinfunction "VSS_K9") (pintype "passive"))
      (node (ref "U2") (pin "N11") (pinfunction "VSS_N11") (pintype "passive"))
      (node (ref "U2") (pin "N2") (pinfunction "VSS_N2") (pintype "passive"))
      (node (ref "U2") (pin "N4") (pinfunction "VSS_N4") (pintype "passive"))
      (node (ref "U2") (pin "N9") (pinfunction "VSS_N9") (pintype "passive"))
      (node (ref "U2") (pin "P1") (pinfunction "VSS_P1") (pintype "passive"))
      (node (ref "U2") (pin "P10") (pinfunction "VSS_P10") (pintype "passive"))
      (node (ref "U2") (pin "P12") (pinfunction "VSS_P12") (pintype "passive"))
      (node (ref "U2") (pin "P3") (pinfunction "VSS_P3") (pintype "passive"))
      (node (ref "U2") (pin "T1") (pinfunction "VSS_T1") (pintype "passive"))
      (node (ref "U2") (pin "T10") (pinfunction "VSS_T10") (pintype "passive"))
      (node (ref "U2") (pin "T12") (pinfunction "VSS_T12") (pintype "passive"))
      (node (ref "U2") (pin "T3") (pinfunction "VSS_T3") (pintype "passive"))
      (node (ref "U2") (pin "T5") (pinfunction "VSS_T5") (pintype "passive"))
      (node (ref "U2") (pin "T8") (pinfunction "VSS_T8") (pintype "passive"))
      (node (ref "U2") (pin "V1") (pinfunction "VSS_V1") (pintype "passive"))
      (node (ref "U2") (pin "V12") (pinfunction "VSS_V12") (pintype "passive"))
      (node (ref "U2") (pin "V5") (pinfunction "VSS_V5") (pintype "passive"))
      (node (ref "U2") (pin "V8") (pinfunction "VSS_V8") (pintype "passive"))
      (node (ref "U2") (pin "W11") (pinfunction "VSS_W11") (pintype "passive"))
      (node (ref "U2") (pin "W2") (pinfunction "VSS_W2") (pintype "passive"))
      (node (ref "U2") (pin "W4") (pinfunction "VSS_W4") (pintype "passive"))
      (node (ref "U2") (pin "W9") (pinfunction "VSS_W9") (pintype "passive"))
      (node (ref "U2") (pin "Y1") (pinfunction "VSS_Y1") (pintype "passive"))
      (node (ref "U2") (pin "Y12") (pinfunction "VSS_Y12") (pintype "passive"))
      (node (ref "U2") (pin "Y5") (pinfunction "VSS_Y5") (pintype "passive"))
      (node (ref "U2") (pin "Y8") (pinfunction "VSS_Y8") (pintype "passive"))
    )
    (net (code "63") (name "Net-(U2A-ODT_CA_A)") (class "Default")
      (node (ref "R5") (pin "1") (pinfunction "1_1") (pintype "passive"))
      (node (ref "U2") (pin "G2") (pinfunction "ODT_CA_A_G2") (pintype "passive"))
    )
    (net (code "64") (name "Net-(U2A-ODT_CA_B)") (class "Default")
      (node (ref "R6") (pin "2") (pinfunction "2_2") (pintype "passive"))
      (node (ref "U2") (pin "T2") (pinfunction "ODT_CA_B_T2") (pintype "passive"))
    )
    (net (code "65") (name "Net-(U2A-ZQ0)") (class "Default")
      (node (ref "R7") (pin "2") (pinfunction "2_2") (pintype "passive"))
      (node (ref "U2") (pin "A5") (pinfunction "ZQ0_A5") (pintype "passive"))
    )
    (net (code "66") (name "Net-(U2A-ZQ1)") (class "Default")
      (node (ref "R8") (pin "2") (pinfunction "2_2") (pintype "passive"))
      (node (ref "U2") (pin "A8") (pinfunction "ZQ1_A8") (pintype "passive"))
    )
    (net (code "67") (name "VDD1") (class "Default")
      (node (ref "C61") (pin "2") (pinfunction "2_2") (pintype "passive"))
      (node (ref "C62") (pin "2") (pinfunction "2_2") (pintype "passive"))
      (node (ref "C63") (pin "2") (pinfunction "2_2") (pintype "passive"))
      (node (ref "C64") (pin "2") (pinfunction "2_2") (pintype "passive"))
      (node (ref "C65") (pin "2") (pinfunction "2_2") (pintype "passive"))
      (node (ref "C66") (pin "2") (pinfunction "2_2") (pintype "passive"))
      (node (ref "C67") (pin "2") (pinfunction "2_2") (pintype "passive"))
      (node (ref "C68") (pin "2") (pinfunction "2_2") (pintype "passive"))
      (node (ref "C69") (pin "2") (pinfunction "2_2") (pintype "passive"))
      (node (ref "C70") (pin "2") (pinfunction "2_2") (pintype "passive"))
      (node (ref "C90") (pin "2") (pinfunction "2_2") (pintype "passive"))
      (node (ref "C91") (pin "2") (pinfunction "2_2") (pintype "passive"))
      (node (ref "C92") (pin "2") (pinfunction "2_2") (pintype "passive"))
      (node (ref "C93") (pin "2") (pinfunction "2_2") (pintype "passive"))
      (node (ref "C94") (pin "2") (pinfunction "2_2") (pintype "passive"))
      (node (ref "C95") (pin "2") (pinfunction "2_2") (pintype "passive"))
      (node (ref "C96") (pin "2") (pinfunction "2_2") (pintype "passive"))
      (node (ref "C97") (pin "2") (pinfunction "2_2") (pintype "passive"))
      (node (ref "C98") (pin "2") (pinfunction "2_2") (pintype "passive"))
      (node (ref "U2") (pin "F1") (pinfunction "VDD1_F1") (pintype "passive"))
      (node (ref "U2") (pin "F12") (pinfunction "VDD1_F12") (pintype "passive"))
      (node (ref "U2") (pin "G4") (pinfunction "VDD1_G4") (pintype "passive"))
      (node (ref "U2") (pin "G9") (pinfunction "VDD1_G9") (pintype "passive"))
      (node (ref "U2") (pin "T4") (pinfunction "VDD1_T4") (pintype "passive"))
      (node (ref "U2") (pin "T9") (pinfunction "VDD1_T9") (pintype "passive"))
      (node (ref "U2") (pin "U1") (pinfunction "VDD1_U1") (pintype "passive"))
      (node (ref "U2") (pin "U12") (pinfunction "VDD1_U12") (pintype "passive"))
    )
    (net (code "68") (name "VDD2") (class "Default")
      (node (ref "C71") (pin "2") (pinfunction "2_2") (pintype "passive"))
      (node (ref "C72") (pin "2") (pinfunction "2_2") (pintype "passive"))
      (node (ref "C73") (pin "2") (pinfunction "2_2") (pintype "passive"))
      (node (ref "C74") (pin "2") (pinfunction "2_2") (pintype "passive"))
      (node (ref "C75") (pin "2") (pinfunction "2_2") (pintype "passive"))
      (node (ref "C76") (pin "2") (pinfunction "2_2") (pintype "passive"))
      (node (ref "C77") (pin "2") (pinfunction "2_2") (pintype "passive"))
      (node (ref "C78") (pin "2") (pinfunction "2_2") (pintype "passive"))
      (node (ref "C79") (pin "2") (pinfunction "2_2") (pintype "passive"))
      (node (ref "C80") (pin "2") (pinfunction "2_2") (pintype "passive"))
      (node (ref "U2") (pin "A4") (pinfunction "VDD2_A4") (pintype "passive"))
      (node (ref "U2") (pin "A9") (pinfunction "VDD2_A9") (pintype "passive"))
      (node (ref "U2") (pin "AB4") (pinfunction "VDD2_AB4") (pintype "passive"))
      (node (ref "U2") (pin "AB9") (pinfunction "VDD2_AB9") (pintype "passive"))
      (node (ref "U2") (pin "F5") (pinfunction "VDD2_F5") (pintype "passive"))
      (node (ref "U2") (pin "F8") (pinfunction "VDD2_F8") (pintype "passive"))
      (node (ref "U2") (pin "H1") (pinfunction "VDD2_H1") (pintype "passive"))
      (node (ref "U2") (pin "H12") (pinfunction "VDD2_H12") (pintype "passive"))
      (node (ref "U2") (pin "H5") (pinfunction "VDD2_H5") (pintype "passive"))
      (node (ref "U2") (pin "H8") (pinfunction "VDD2_H8") (pintype "passive"))
      (node (ref "U2") (pin "K1") (pinfunction "VDD2_K1") (pintype "passive"))
      (node (ref "U2") (pin "K10") (pinfunction "VDD2_K10") (pintype "passive"))
      (node (ref "U2") (pin "K12") (pinfunction "VDD2_K12") (pintype "passive"))
      (node (ref "U2") (pin "K3") (pinfunction "VDD2_K3") (pintype "passive"))
      (node (ref "U2") (pin "N1") (pinfunction "VDD2_N1") (pintype "passive"))
      (node (ref "U2") (pin "N10") (pinfunction "VDD2_N10") (pintype "passive"))
      (node (ref "U2") (pin "N12") (pinfunction "VDD2_N12") (pintype "passive"))
      (node (ref "U2") (pin "N3") (pinfunction "VDD2_N3") (pintype "passive"))
      (node (ref "U2") (pin "R1") (pinfunction "VDD2_R1") (pintype "passive"))
      (node (ref "U2") (pin "R12") (pinfunction "VDD2_R12") (pintype "passive"))
      (node (ref "U2") (pin "R5") (pinfunction "VDD2_R5") (pintype "passive"))
      (node (ref "U2") (pin "R8") (pinfunction "VDD2_R8") (pintype "passive"))
      (node (ref "U2") (pin "U5") (pinfunction "VDD2_U5") (pintype "passive"))
      (node (ref "U2") (pin "U8") (pinfunction "VDD2_U8") (pintype "passive"))
    )
    (net (code "69") (name "VDDQ") (class "Default")
      (node (ref "C51") (pin "2") (pinfunction "2_2") (pintype "passive"))
      (node (ref "C52") (pin "2") (pinfunction "2_2") (pintype "passive"))
      (node (ref "C53") (pin "2") (pinfunction "2_2") (pintype "passive"))
      (node (ref "C54") (pin "2") (pinfunction "2_2") (pintype "passive"))
      (node (ref "C55") (pin "2") (pinfunction "2_2") (pintype "passive"))
      (node (ref "C56") (pin "2") (pinfunction "2_2") (pintype "passive"))
      (node (ref "C57") (pin "2") (pinfunction "2_2") (pintype "passive"))
      (node (ref "C58") (pin "2") (pinfunction "2_2") (pintype "passive"))
      (node (ref "C59") (pin "2") (pinfunction "2_2") (pintype "passive"))
      (node (ref "C60") (pin "2") (pinfunction "2_2") (pintype "passive"))
      (node (ref "C81") (pin "2") (pinfunction "2_2") (pintype "passive"))
      (node (ref "C82") (pin "2") (pinfunction "2_2") (pintype "passive"))
      (node (ref "C83") (pin "2") (pinfunction "2_2") (pintype "passive"))
      (node (ref "C84") (pin "2") (pinfunction "2_2") (pintype "passive"))
      (node (ref "C85") (pin "2") (pinfunction "2_2") (pintype "passive"))
      (node (ref "C86") (pin "2") (pinfunction "2_2") (pintype "passive"))
      (node (ref "C87") (pin "2") (pinfunction "2_2") (pintype "passive"))
      (node (ref "C88") (pin "2") (pinfunction "2_2") (pintype "passive"))
      (node (ref "C89") (pin "2") (pinfunction "2_2") (pintype "passive"))
      (node (ref "R5") (pin "2") (pinfunction "2_2") (pintype "passive"))
      (node (ref "R7") (pin "1") (pinfunction "1_1") (pintype "passive"))
      (node (ref "R8") (pin "1") (pinfunction "1_1") (pintype "passive"))
      (node (ref "U2") (pin "AA10") (pinfunction "VDDQ_AA10") (pintype "passive"))
      (node (ref "U2") (pin "AA3") (pinfunction "VDDQ_AA3") (pintype "passive"))
      (node (ref "U2") (pin "AA5") (pinfunction "VDDQ_AA5") (pintype "passive"))
      (node (ref "U2") (pin "AA8") (pinfunction "VDDQ_AA8") (pintype "passive"))
      (node (ref "U2") (pin "B10") (pinfunction "VDDQ_B10") (pintype "passive"))
      (node (ref "U2") (pin "B3") (pinfunction "VDDQ_B3") (pintype "passive"))
      (node (ref "U2") (pin "B5") (pinfunction "VDDQ_B5") (pintype "passive"))
      (node (ref "U2") (pin "B8") (pinfunction "VDDQ_B8") (pintype "passive"))
      (node (ref "U2") (pin "D1") (pinfunction "VDDQ_D1") (pintype "passive"))
      (node (ref "U2") (pin "D12") (pinfunction "VDDQ_D12") (pintype "passive"))
      (node (ref "U2") (pin "D5") (pinfunction "VDDQ_D5") (pintype "passive"))
      (node (ref "U2") (pin "D8") (pinfunction "VDDQ_D8") (pintype "passive"))
      (node (ref "U2") (pin "F10") (pinfunction "VDDQ_F10") (pintype "passive"))
      (node (ref "U2") (pin "F3") (pinfunction "VDDQ_F3") (pintype "passive"))
      (node (ref "U2") (pin "U10") (pinfunction "VDDQ_U10") (pintype "passive"))
      (node (ref "U2") (pin "U3") (pinfunction "VDDQ_U3") (pintype "passive"))
      (node (ref "U2") (pin "W1") (pinfunction "VDDQ_W1") (pintype "passive"))
      (node (ref "U2") (pin "W12") (pinfunction "VDDQ_W12") (pintype "passive"))
      (node (ref "U2") (pin "W5") (pinfunction "VDDQ_W5") (pintype "passive"))
      (node (ref "U2") (pin "W8") (pinfunction "VDDQ_W8") (pintype "passive"))
    )
    (net (code "70") (name "unconnected-(U2B-DNU1-PadA1)") (class "Default")
      (node (ref "U2") (pin "A1") (pinfunction "DNU1_A1") (pintype "passive+no_connect"))
    )
    (net (code "71") (name "unconnected-(U2B-DNU2-PadA2)") (class "Default")
      (node (ref "U2") (pin "A2") (pinfunction "DNU2_A2") (pintype "passive+no_connect"))
    )
    (net (code "72") (name "unconnected-(U2B-DNU3-PadA11)") (class "Default")
      (node (ref "U2") (pin "A11") (pinfunction "DNU3_A11") (pintype "passive+no_connect"))
    )
    (net (code "73") (name "unconnected-(U2B-DNU4-PadA12)") (class "Default")
      (node (ref "U2") (pin "A12") (pinfunction "DNU4_A12") (pintype "passive+no_connect"))
    )
    (net (code "74") (name "unconnected-(U2B-DNU5-PadB1)") (class "Default")
      (node (ref "U2") (pin "B1") (pinfunction "DNU5_B1") (pintype "passive+no_connect"))
    )
    (net (code "75") (name "unconnected-(U2B-DNU6-PadB12)") (class "Default")
      (node (ref "U2") (pin "B12") (pinfunction "DNU6_B12") (pintype "passive+no_connect"))
    )
    (net (code "76") (name "unconnected-(U2B-DNU7-PadAA1)") (class "Default")
      (node (ref "U2") (pin "AA1") (pinfunction "DNU7_AA1") (pintype "passive+no_connect"))
    )
    (net (code "77") (name "unconnected-(U2B-DNU8-PadAA12)") (class "Default")
      (node (ref "U2") (pin "AA12") (pinfunction "DNU8_AA12") (pintype "passive+no_connect"))
    )
    (net (code "78") (name "unconnected-(U2B-DNU9-PadAB1)") (class "Default")
      (node (ref "U2") (pin "AB1") (pinfunction "DNU9_AB1") (pintype "passive+no_connect"))
    )
    (net (code "79") (name "unconnected-(U2B-DNU10-PadAB2)") (class "Default")
      (node (ref "U2") (pin "AB2") (pinfunction "DNU10_AB2") (pintype "passive+no_connect"))
    )
    (net (code "80") (name "unconnected-(U2B-DNU11-PadAB11)") (class "Default")
      (node (ref "U2") (pin "AB11") (pinfunction "DNU11_AB11") (pintype "passive+no_connect"))
    )
    (net (code "81") (name "unconnected-(U2B-DNU12-PadAB12)") (class "Default")
      (node (ref "U2") (pin "AB12") (pinfunction "DNU12_AB12") (pintype "passive+no_connect"))
    )
    (net (code "82") (name "unconnected-(U2B-DNU13-PadK8)") (class "Default")
      (node (ref "U2") (pin "K8") (pinfunction "DNU13_K8") (pintype "passive+no_connect"))
    )
    (net (code "83") (name "unconnected-(U2B-DNU14-PadN5)") (class "Default")
      (node (ref "U2") (pin "N5") (pinfunction "DNU14_N5") (pintype "passive+no_connect"))
    )
    (net (code "84") (name "unconnected-(U2B-DNU15-PadK5)") (class "Default")
      (node (ref "U2") (pin "K5") (pinfunction "DNU15_K5") (pintype "passive+no_connect"))
    )
    (net (code "85") (name "unconnected-(U2B-DNU16-PadG11)") (class "Default")
      (node (ref "U2") (pin "G11") (pinfunction "DNU16_G11") (pintype "passive+no_connect"))
    )
    (net (code "86") (name "unconnected-(U2B-DNU17-PadN8)") (class "Default")
      (node (ref "U2") (pin "N8") (pinfunction "DNU17_N8") (pintype "passive+no_connect"))
    )
  )
)
